# LOC_BUI.net
KiCad netlist of a schematic drawn in Altium Designer
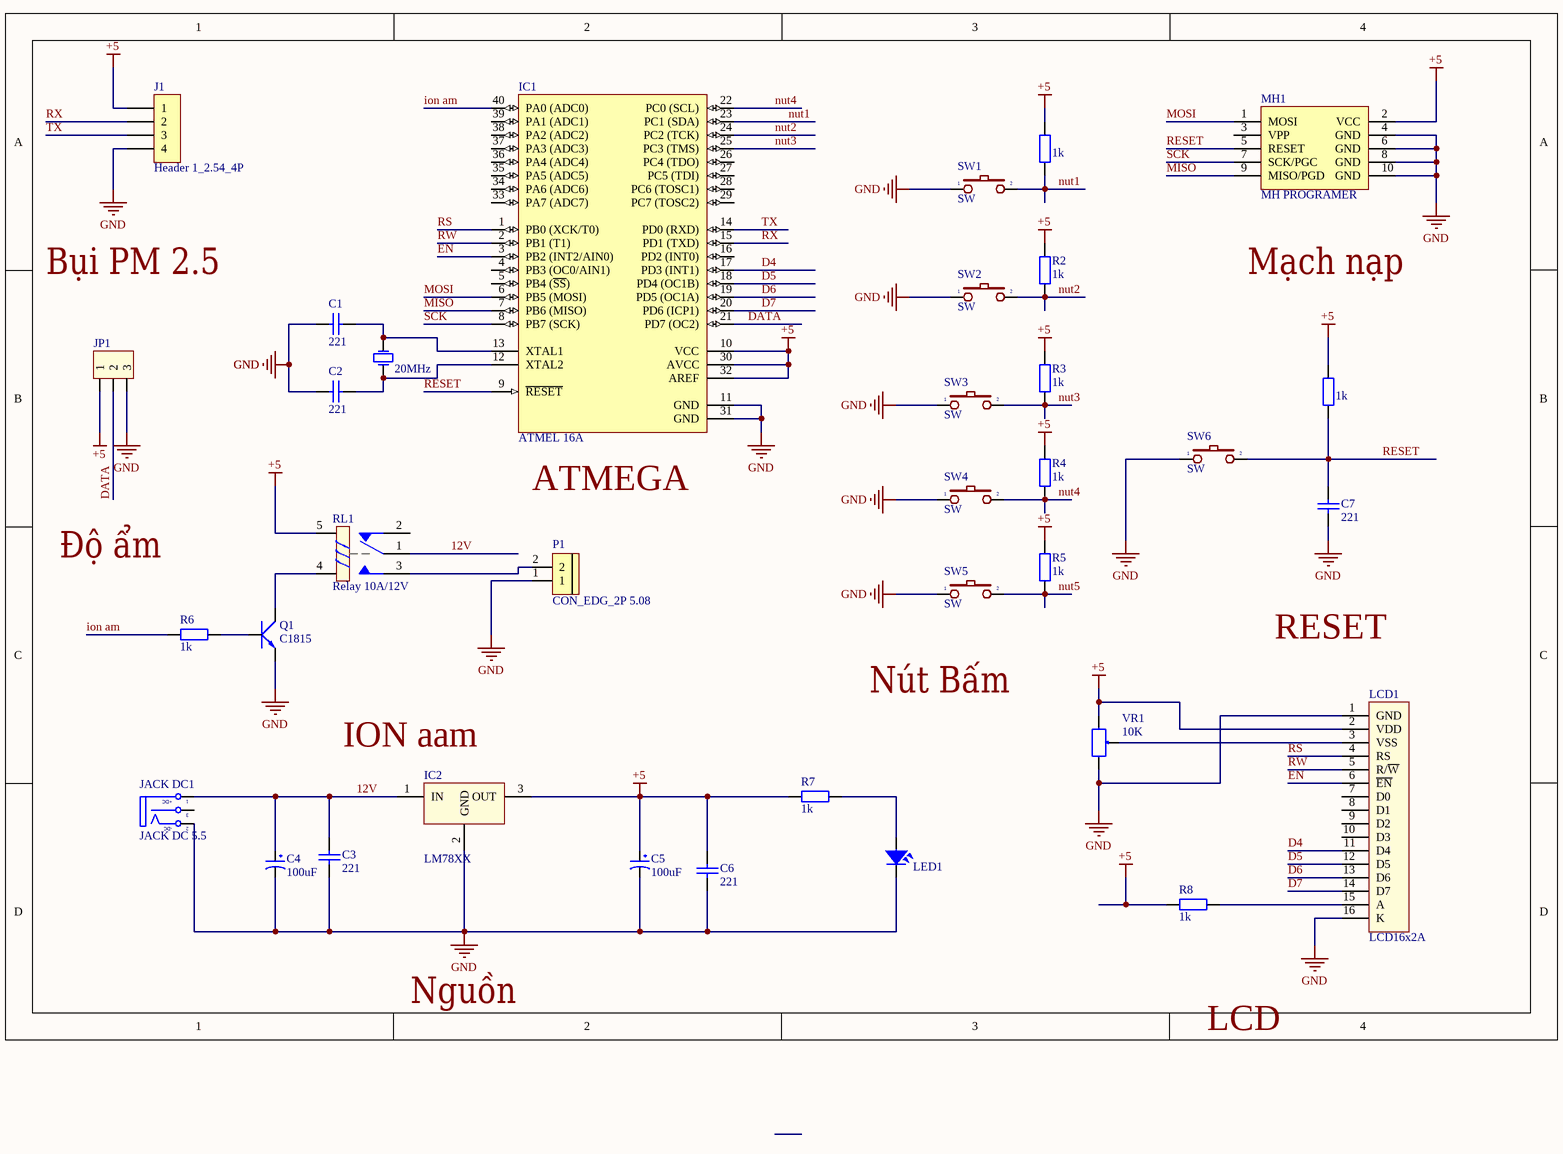
[diagram p0: LOC_BUI.SchDoc]

(export (version "E")
  (design (tool "Eeschema 10.0.6"))
  (components
    (comp (ref "C1")
      (value "221")
      (footprint "tu 0805")
      (description "Dán")
      (libsource (lib "THU VIEN SCH") (part "Tu 0805 221 50V"))
    )
    (comp (ref "C2")
      (value "221")
      (footprint "tu 0805")
      (description "Dán")
      (libsource (lib "THU VIEN SCH") (part "Tu 0805 221 50V"))
    )
    (comp (ref "C3")
      (value "221")
      (footprint "tu 0805")
      (description "Dán")
      (libsource (lib "THU VIEN SCH") (part "Tu 0805 221 50V"))
    )
    (comp (ref "C4")
      (value "100uF")
      (footprint "CP1/2.5")
      (description "C 47uF/50V , 220uF/16V")
      (libsource (lib "Thu Vien Chuan") (part "CP2"))
    )
    (comp (ref "C5")
      (value "100uF")
      (footprint "CP1/2.5")
      (description "C 47uF/50V , 220uF/16V")
      (libsource (lib "Thu Vien Chuan") (part "CP2"))
    )
    (comp (ref "C6")
      (value "221")
      (footprint "tu 0805")
      (description "Dán")
      (libsource (lib "THU VIEN SCH") (part "Tu 0805 221 50V"))
    )
    (comp (ref "C7")
      (value "221")
      (footprint "tu 0805")
      (description "Dán")
      (libsource (lib "THU VIEN SCH") (part "Tu 0805 221 50V"))
    )
    (comp (ref "IC1")
      (value "ATMEL 16A")
      (footprint "DIP40/W0.6")
      (description "8-Bit AVR Microcontroller with 16K Bytes of In-System Programmable Flash Memory")
      (libsource (lib "Thu Vien Chuan") (part "ATmega16A-PU"))
    )
    (comp (ref "IC2")
      (value "LM78XX")
      (footprint "QTO-220")
      (description "On ap +, from + 5 to + 24VDC")
      (libsource (lib "Thu Vien Chuan") (part "LM78XX"))
    )
    (comp (ref "J1")
      (value "Header 1_2.54_4P")
      (footprint "Header_Duc Cong_4P 2.54")
      (description "Cắm")
      (libsource (lib "THU VIEN SCH") (part "Header 1_2.54_4P"))
    )
    (comp (ref "JACK DC1")
      (value "JACK DC 5.5")
      (footprint "JACK DC 5.5")
      (libsource (lib "Thu Vien Chuan") (part "JACK DC 5.5"))
    )
    (comp (ref "JP1")
      (value "~")
      (footprint "XH2.54-3P")
      (description "Connector 3")
      (libsource (lib "Thu Vien Chuan") (part "Header 3P Duc Thang"))
    )
    (comp (ref "LCD1")
      (value "LCD16x2A")
      (footprint "LCD16X2")
      (description "JUMP DON CAI")
      (libsource (lib "Thu Vien Chuan") (part "LCD16X2"))
    )
    (comp (ref "LED1")
      (value "LED")
      (footprint "LED-3")
      (description "LED Single colour Green and Red")
      (libsource (lib "Thu Vien Chuan") (part "LED"))
    )
    (comp (ref "MH1")
      (value "MH PROGRAMER")
      (footprint "CABLE 10")
      (libsource (lib "Thu Vien Chuan") (part "MH PRO"))
    )
    (comp (ref "P1")
      (value "CON_EDG_2P 5.08")
      (footprint "CON 2 2EDG5.08")
      (description "Cắm")
      (libsource (lib "THU VIEN SCH") (part "CON_EDG_2P 5.08"))
    )
    (comp (ref "Q1")
      (value "C1815")
      (footprint "QTO-92")
      (description "NPN 600mW, ECB")
      (libsource (lib "Thu Vien Chuan") (part "C1815_1"))
    )
    (comp (ref "R1")
      (value "1k")
      (footprint "tro smd 0805")
      (description "Dán")
      (libsource (lib "THU VIEN SCH") (part "Tro 0805 1% 1k"))
    )
    (comp (ref "R2")
      (value "1k")
      (footprint "tro smd 0805")
      (description "Dán")
      (libsource (lib "THU VIEN SCH") (part "Tro 0805 5% 1k"))
    )
    (comp (ref "R3")
      (value "1k")
      (footprint "tro smd 0805")
      (description "Dán")
      (libsource (lib "THU VIEN SCH") (part "Tro 0805 5% 1k"))
    )
    (comp (ref "R4")
      (value "1k")
      (footprint "tro smd 0805")
      (description "Dán")
      (libsource (lib "THU VIEN SCH") (part "Tro 0805 5% 1k"))
    )
    (comp (ref "R5")
      (value "1k")
      (footprint "tro smd 0805")
      (description "Dán")
      (libsource (lib "THU VIEN SCH") (part "Tro 0805 5% 1k"))
    )
    (comp (ref "R6")
      (value "1k")
      (footprint "tro smd 0805")
      (description "Dán")
      (libsource (lib "THU VIEN SCH") (part "Tro 0805 5% 1k"))
    )
    (comp (ref "R7")
      (value "1k")
      (footprint "tro smd 0805")
      (description "Dán")
      (libsource (lib "THU VIEN SCH") (part "Tro 0805 5% 1k"))
    )
    (comp (ref "R8")
      (value "1k")
      (footprint "tro smd 0805")
      (description "Dán")
      (libsource (lib "THU VIEN SCH") (part "Tro 0805 5% 1k"))
    )
    (comp (ref "R9")
      (value "1k")
      (footprint "tro smd 0805")
      (description "Dán")
      (libsource (lib "THU VIEN SCH") (part "Tro 0805 1% 1k"))
    )
    (comp (ref "RL1")
      (value "Relay 10A/12V")
      (footprint "RL_SPDT_10A")
      (description "Relay SPDT,10A - 12VDC 5 Pin")
      (libsource (lib "Thu Vien Chuan") (part "Relay 1"))
    )
    (comp (ref "SW1")
      (value "SW")
      (footprint "SW2")
      (description "Switch button 2 pin")
      (libsource (lib "Thu Vien Chuan") (part "SW2"))
    )
    (comp (ref "SW2")
      (value "SW")
      (footprint "SW2")
      (description "Switch button 2 pin")
      (libsource (lib "Thu Vien Chuan") (part "SW2"))
    )
    (comp (ref "SW3")
      (value "SW")
      (footprint "SW2")
      (description "Switch button 2 pin")
      (libsource (lib "Thu Vien Chuan") (part "SW2"))
    )
    (comp (ref "SW4")
      (value "SW")
      (footprint "SW2")
      (description "Switch button 2 pin")
      (libsource (lib "Thu Vien Chuan") (part "SW2"))
    )
    (comp (ref "SW5")
      (value "SW")
      (footprint "SW2")
      (description "Switch button 2 pin")
      (libsource (lib "Thu Vien Chuan") (part "SW2"))
    )
    (comp (ref "SW6")
      (value "SW")
      (footprint "SW2")
      (description "Switch button 2 pin")
      (libsource (lib "Thu Vien Chuan") (part "SW2"))
    )
    (comp (ref "VR1")
      (value "10K")
      (footprint "VR")
      (description "Var Resistor")
      (libsource (lib "Thu Vien Chuan") (part "VR"))
    )
    (comp (ref "x1")
      (value "20MHz")
      (footprint "Thach anh cam")
      (description "Crystal Oscillator")
      (fields (field (name "PUBLISHER") "Altium Limited"))
      (libsource (lib "Thu Vien Chuan") (part "Crystal"))
    )
  )
  (nets
    (net (code "1") (name "+5") (class "Default")
      (node (ref "C5") (pin "1") (pinfunction "1_1") (pintype "passive"))
      (node (ref "C6") (pin "1") (pinfunction "1_1") (pintype "passive"))
      (node (ref "IC1") (pin "10") (pinfunction "VCC_10") (pintype "power_in"))
      (node (ref "IC1") (pin "30") (pinfunction "AVCC_30") (pintype "power_in"))
      (node (ref "IC1") (pin "32") (pinfunction "AREF_32") (pintype "power_in"))
      (node (ref "IC2") (pin "3") (pinfunction "OUT_3") (pintype "passive"))
      (node (ref "J1") (pin "1") (pinfunction "1_1") (pintype "passive"))
      (node (ref "JP1") (pin "1") (pinfunction "1_1") (pintype "passive"))
      (node (ref "LCD1") (pin "2") (pinfunction "VDD_2") (pintype "passive"))
      (node (ref "MH1") (pin "2") (pinfunction "VCC_2") (pintype "passive"))
      (node (ref "R1") (pin "2") (pinfunction "2_2") (pintype "passive"))
      (node (ref "R2") (pin "2") (pinfunction "2_2") (pintype "passive"))
      (node (ref "R3") (pin "2") (pinfunction "2_2") (pintype "passive"))
      (node (ref "R4") (pin "2") (pinfunction "2_2") (pintype "passive"))
      (node (ref "R5") (pin "2") (pinfunction "2_2") (pintype "passive"))
      (node (ref "R7") (pin "2") (pinfunction "2_2") (pintype "passive"))
      (node (ref "R8") (pin "2") (pinfunction "2_2") (pintype "passive"))
      (node (ref "R9") (pin "2") (pinfunction "2_2") (pintype "passive"))
      (node (ref "RL1") (pin "5") (pinfunction "5_5") (pintype "passive"))
      (node (ref "VR1") (pin "1") (pinfunction "1_1") (pintype "passive"))
    )
    (net (code "2") (name "/12V") (class "Default")
      (node (ref "C3") (pin "1") (pinfunction "1_1") (pintype "passive"))
      (node (ref "C4") (pin "1") (pinfunction "1_1") (pintype "passive"))
      (node (ref "IC2") (pin "1") (pinfunction "IN_1") (pintype "passive"))
      (node (ref "JACK DC1") (pin "1") (pinfunction "T_1") (pintype "passive"))
      (node (ref "RL1") (pin "1") (pinfunction "1_1") (pintype "passive"))
    )
    (net (code "5") (name "/D4") (class "Default")
      (node (ref "IC1") (pin "17") (pinfunction "PD3_(INT1)_17") (pintype "bidirectional"))
      (node (ref "LCD1") (pin "11") (pinfunction "D4_11") (pintype "passive"))
    )
    (net (code "6") (name "/D5") (class "Default")
      (node (ref "IC1") (pin "18") (pinfunction "PD4_(OC1B)_18") (pintype "bidirectional"))
      (node (ref "LCD1") (pin "12") (pinfunction "D5_12") (pintype "passive"))
    )
    (net (code "7") (name "/D6") (class "Default")
      (node (ref "IC1") (pin "19") (pinfunction "PD5_(OC1A)_19") (pintype "bidirectional"))
      (node (ref "LCD1") (pin "13") (pinfunction "D6_13") (pintype "passive"))
    )
    (net (code "8") (name "/D7") (class "Default")
      (node (ref "IC1") (pin "20") (pinfunction "PD6_(ICP1)_20") (pintype "bidirectional"))
      (node (ref "LCD1") (pin "14") (pinfunction "D7_14") (pintype "passive"))
    )
    (net (code "9") (name "/DATA") (class "Default")
      (node (ref "IC1") (pin "21") (pinfunction "PD7_(OC2)_21") (pintype "bidirectional"))
      (node (ref "JP1") (pin "2") (pinfunction "2_2") (pintype "passive"))
    )
    (net (code "10") (name "/EN") (class "Default")
      (node (ref "IC1") (pin "3") (pinfunction "PB2_(INT2/AIN0)_3") (pintype "bidirectional"))
      (node (ref "LCD1") (pin "6") (pinfunction "~{EN}_6") (pintype "passive"))
    )
    (net (code "13") (name "/MISO") (class "Default")
      (node (ref "IC1") (pin "7") (pinfunction "PB6_(MISO)_7") (pintype "bidirectional"))
      (node (ref "MH1") (pin "9") (pinfunction "MISO/PGD_9") (pintype "passive"))
    )
    (net (code "14") (name "/MOSI") (class "Default")
      (node (ref "IC1") (pin "6") (pinfunction "PB5_(MOSI)_6") (pintype "bidirectional"))
      (node (ref "MH1") (pin "1") (pinfunction "MOSI_1") (pintype "passive"))
    )
    (net (code "18") (name "/RESET") (class "Default")
      (node (ref "C7") (pin "1") (pinfunction "1_1") (pintype "passive"))
      (node (ref "IC1") (pin "9") (pinfunction "~{RESET}_9") (pintype "input"))
      (node (ref "MH1") (pin "5") (pinfunction "RESET_5") (pintype "passive"))
      (node (ref "R9") (pin "1") (pinfunction "1_1") (pintype "passive"))
      (node (ref "SW6") (pin "2") (pinfunction "2_2") (pintype "passive"))
    )
    (net (code "19") (name "/RS") (class "Default")
      (node (ref "IC1") (pin "1") (pinfunction "PB0_(XCK/T0)_1") (pintype "bidirectional"))
      (node (ref "LCD1") (pin "4") (pinfunction "RS_4") (pintype "passive"))
    )
    (net (code "20") (name "/RW") (class "Default")
      (node (ref "IC1") (pin "2") (pinfunction "PB1_(T1)_2") (pintype "bidirectional"))
      (node (ref "LCD1") (pin "5") (pinfunction "R/~{W}_5") (pintype "passive"))
    )
    (net (code "21") (name "/RX") (class "Default")
      (node (ref "IC1") (pin "15") (pinfunction "PD1_(TXD)_15") (pintype "bidirectional"))
      (node (ref "J1") (pin "2") (pinfunction "2_2") (pintype "passive"))
    )
    (net (code "22") (name "/SCK") (class "Default")
      (node (ref "IC1") (pin "8") (pinfunction "PB7_(SCK)_8") (pintype "bidirectional"))
      (node (ref "MH1") (pin "7") (pinfunction "SCK/PGC_7") (pintype "passive"))
    )
    (net (code "23") (name "/TX") (class "Default")
      (node (ref "IC1") (pin "14") (pinfunction "PD0_(RXD)_14") (pintype "bidirectional"))
      (node (ref "J1") (pin "3") (pinfunction "3_3") (pintype "passive"))
    )
    (net (code "24") (name "/ion am") (class "Default")
      (node (ref "IC1") (pin "40") (pinfunction "PA0_(ADC0)_40") (pintype "bidirectional"))
      (node (ref "R6") (pin "2") (pinfunction "2_2") (pintype "passive"))
    )
    (net (code "25") (name "/nut1") (class "Default")
      (node (ref "IC1") (pin "23") (pinfunction "PC1_(SDA)_23") (pintype "bidirectional"))
      (node (ref "R1") (pin "1") (pinfunction "1_1") (pintype "passive"))
      (node (ref "SW1") (pin "2") (pinfunction "2_2") (pintype "passive"))
    )
    (net (code "26") (name "/nut2") (class "Default")
      (node (ref "IC1") (pin "24") (pinfunction "PC2_(TCK)_24") (pintype "bidirectional"))
      (node (ref "R2") (pin "1") (pinfunction "1_1") (pintype "passive"))
      (node (ref "SW2") (pin "2") (pinfunction "2_2") (pintype "passive"))
    )
    (net (code "27") (name "/nut3") (class "Default")
      (node (ref "IC1") (pin "25") (pinfunction "PC3_(TMS)_25") (pintype "bidirectional"))
      (node (ref "R3") (pin "1") (pinfunction "1_1") (pintype "passive"))
      (node (ref "SW3") (pin "2") (pinfunction "2_2") (pintype "passive"))
    )
    (net (code "28") (name "/nut4") (class "Default")
      (node (ref "IC1") (pin "22") (pinfunction "PC0_(SCL)_22") (pintype "bidirectional"))
      (node (ref "R4") (pin "1") (pinfunction "1_1") (pintype "passive"))
      (node (ref "SW4") (pin "2") (pinfunction "2_2") (pintype "passive"))
    )
    (net (code "29") (name "/nut5") (class "Default")
      (node (ref "R5") (pin "1") (pinfunction "1_1") (pintype "passive"))
      (node (ref "SW5") (pin "2") (pinfunction "2_2") (pintype "passive"))
    )
    (net (code "31") (name "GND") (class "Default")
      (node (ref "C1") (pin "2") (pinfunction "2_2") (pintype "passive"))
      (node (ref "C2") (pin "2") (pinfunction "2_2") (pintype "passive"))
      (node (ref "C3") (pin "2") (pinfunction "2_2") (pintype "passive"))
      (node (ref "C4") (pin "2") (pinfunction "2_2") (pintype "passive"))
      (node (ref "C5") (pin "2") (pinfunction "2_2") (pintype "passive"))
      (node (ref "C6") (pin "2") (pinfunction "2_2") (pintype "passive"))
      (node (ref "C7") (pin "2") (pinfunction "2_2") (pintype "passive"))
      (node (ref "IC1") (pin "11") (pinfunction "GND_11") (pintype "power_in"))
      (node (ref "IC1") (pin "31") (pinfunction "GND_31") (pintype "power_in"))
      (node (ref "IC2") (pin "2") (pinfunction "GND_2") (pintype "passive"))
      (node (ref "J1") (pin "4") (pinfunction "4_4") (pintype "passive"))
      (node (ref "JACK DC1") (pin "2") (pinfunction "TN_2") (pintype "passive"))
      (node (ref "JP1") (pin "3") (pinfunction "3_3") (pintype "passive"))
      (node (ref "LCD1") (pin "1") (pinfunction "GND_1") (pintype "passive"))
      (node (ref "LCD1") (pin "16") (pinfunction "K_16") (pintype "passive"))
      (node (ref "LED1") (pin "2") (pinfunction "2_2") (pintype "passive"))
      (node (ref "MH1") (pin "10") (pinfunction "GND_10") (pintype "passive"))
      (node (ref "MH1") (pin "4") (pinfunction "GND_4") (pintype "passive"))
      (node (ref "MH1") (pin "6") (pinfunction "GND_6") (pintype "passive"))
      (node (ref "MH1") (pin "8") (pinfunction "GND_8") (pintype "passive"))
      (node (ref "P1") (pin "1") (pinfunction "1_1") (pintype "passive"))
      (node (ref "Q1") (pin "1") (pinfunction "E_1") (pintype "passive"))
      (node (ref "SW1") (pin "1") (pinfunction "1_1") (pintype "passive"))
      (node (ref "SW2") (pin "1") (pinfunction "1_1") (pintype "passive"))
      (node (ref "SW3") (pin "1") (pinfunction "1_1") (pintype "passive"))
      (node (ref "SW4") (pin "1") (pinfunction "1_1") (pintype "passive"))
      (node (ref "SW5") (pin "1") (pinfunction "1_1") (pintype "passive"))
      (node (ref "SW6") (pin "1") (pinfunction "1_1") (pintype "passive"))
      (node (ref "VR1") (pin "3") (pinfunction "3_3") (pintype "passive"))
    )
    (net (code "32") (name "Net-(IC1-XTAL1)") (class "Default")
      (node (ref "C1") (pin "1") (pinfunction "1_1") (pintype "passive"))
      (node (ref "IC1") (pin "13") (pinfunction "XTAL1_13") (pintype "passive"))
      (node (ref "x1") (pin "1") (pinfunction "OSC1_1") (pintype "passive"))
    )
    (net (code "33") (name "Net-(IC1-XTAL2)") (class "Default")
      (node (ref "C2") (pin "1") (pinfunction "1_1") (pintype "passive"))
      (node (ref "IC1") (pin "12") (pinfunction "XTAL2_12") (pintype "passive"))
      (node (ref "x1") (pin "2") (pinfunction "OSC2_2") (pintype "passive"))
    )
    (net (code "34") (name "Net-(LCD1-A)") (class "Default")
      (node (ref "LCD1") (pin "15") (pinfunction "A_15") (pintype "passive"))
      (node (ref "R8") (pin "1") (pinfunction "1_1") (pintype "passive"))
    )
    (net (code "35") (name "Net-(LCD1-VSS)") (class "Default")
      (node (ref "LCD1") (pin "3") (pinfunction "VSS_3") (pintype "passive"))
      (node (ref "VR1") (pin "2") (pinfunction "2_2") (pintype "passive"))
    )
    (net (code "36") (name "Net-(LED1-Pad1)") (class "Default")
      (node (ref "LED1") (pin "1") (pinfunction "1_1") (pintype "passive"))
      (node (ref "R7") (pin "1") (pinfunction "1_1") (pintype "passive"))
    )
    (net (code "37") (name "Net-(P1-Pad2)") (class "Default")
      (node (ref "P1") (pin "2") (pinfunction "2_2") (pintype "passive"))
      (node (ref "RL1") (pin "3") (pinfunction "3_3") (pintype "passive"))
    )
    (net (code "38") (name "Net-(Q1-B)") (class "Default")
      (node (ref "Q1") (pin "3") (pinfunction "B_3") (pintype "passive"))
      (node (ref "R6") (pin "1") (pinfunction "1_1") (pintype "passive"))
    )
    (net (code "39") (name "Net-(Q1-C)") (class "Default")
      (node (ref "Q1") (pin "2") (pinfunction "C_2") (pintype "passive"))
      (node (ref "RL1") (pin "4") (pinfunction "4_4") (pintype "passive"))
    )
    (net (code "40") (name "unconnected-(IC1-PA1_(ADC1)-Pad39)") (class "Default")
      (node (ref "IC1") (pin "39") (pinfunction "PA1_(ADC1)_39") (pintype "bidirectional"))
    )
    (net (code "41") (name "unconnected-(IC1-PA2_(ADC2)-Pad38)") (class "Default")
      (node (ref "IC1") (pin "38") (pinfunction "PA2_(ADC2)_38") (pintype "bidirectional"))
    )
    (net (code "42") (name "unconnected-(IC1-PA3_(ADC3)-Pad37)") (class "Default")
      (node (ref "IC1") (pin "37") (pinfunction "PA3_(ADC3)_37") (pintype "bidirectional"))
    )
    (net (code "43") (name "unconnected-(IC1-PA4_(ADC4)-Pad36)") (class "Default")
      (node (ref "IC1") (pin "36") (pinfunction "PA4_(ADC4)_36") (pintype "bidirectional"))
    )
    (net (code "44") (name "unconnected-(IC1-PA5_(ADC5)-Pad35)") (class "Default")
      (node (ref "IC1") (pin "35") (pinfunction "PA5_(ADC5)_35") (pintype "bidirectional"))
    )
    (net (code "45") (name "unconnected-(IC1-PA6_(ADC6)-Pad34)") (class "Default")
      (node (ref "IC1") (pin "34") (pinfunction "PA6_(ADC6)_34") (pintype "bidirectional"))
    )
    (net (code "46") (name "unconnected-(IC1-PA7_(ADC7)-Pad33)") (class "Default")
      (node (ref "IC1") (pin "33") (pinfunction "PA7_(ADC7)_33") (pintype "bidirectional"))
    )
    (net (code "47") (name "unconnected-(IC1-PB3_(OC0{slash}AIN1)-Pad4)") (class "Default")
      (node (ref "IC1") (pin "4") (pinfunction "PB3_(OC0/AIN1)_4") (pintype "bidirectional"))
    )
    (net (code "48") (name "unconnected-(IC1-PB4_(~{SS})-Pad5)") (class "Default")
      (node (ref "IC1") (pin "5") (pinfunction "PB4_(~{SS})_5") (pintype "bidirectional"))
    )
    (net (code "49") (name "unconnected-(IC1-PC4_(TDO)-Pad26)") (class "Default")
      (node (ref "IC1") (pin "26") (pinfunction "PC4_(TDO)_26") (pintype "bidirectional"))
    )
    (net (code "50") (name "unconnected-(IC1-PC5_(TDI)-Pad27)") (class "Default")
      (node (ref "IC1") (pin "27") (pinfunction "PC5_(TDI)_27") (pintype "bidirectional"))
    )
    (net (code "51") (name "unconnected-(IC1-PC6_(TOSC1)-Pad28)") (class "Default")
      (node (ref "IC1") (pin "28") (pinfunction "PC6_(TOSC1)_28") (pintype "bidirectional"))
    )
    (net (code "52") (name "unconnected-(IC1-PC7_(TOSC2)-Pad29)") (class "Default")
      (node (ref "IC1") (pin "29") (pinfunction "PC7_(TOSC2)_29") (pintype "bidirectional"))
    )
    (net (code "53") (name "unconnected-(IC1-PD2_(INT0)-Pad16)") (class "Default")
      (node (ref "IC1") (pin "16") (pinfunction "PD2_(INT0)_16") (pintype "bidirectional"))
    )
    (net (code "54") (name "unconnected-(JACK DC1-S-Pad3)") (class "Default")
      (node (ref "JACK DC1") (pin "3") (pinfunction "S_3") (pintype "power_in"))
    )
    (net (code "55") (name "unconnected-(LCD1-D0-Pad7)") (class "Default")
      (node (ref "LCD1") (pin "7") (pinfunction "D0_7") (pintype "passive"))
    )
    (net (code "56") (name "unconnected-(LCD1-D1-Pad8)") (class "Default")
      (node (ref "LCD1") (pin "8") (pinfunction "D1_8") (pintype "passive"))
    )
    (net (code "57") (name "unconnected-(LCD1-D2-Pad9)") (class "Default")
      (node (ref "LCD1") (pin "9") (pinfunction "D2_9") (pintype "passive"))
    )
    (net (code "58") (name "unconnected-(LCD1-D3-Pad10)") (class "Default")
      (node (ref "LCD1") (pin "10") (pinfunction "D3_10") (pintype "passive"))
    )
    (net (code "59") (name "unconnected-(MH1-VPP-Pad3)") (class "Default")
      (node (ref "MH1") (pin "3") (pinfunction "VPP_3") (pintype "passive"))
    )
    (net (code "60") (name "unconnected-(RL1-Pad2)") (class "Default")
      (node (ref "RL1") (pin "2") (pinfunction "2_2") (pintype "passive"))
    )
  )
)
